# One-Wire_Write_Read.net
KiCad netlist of a schematic drawn in Altium Designer
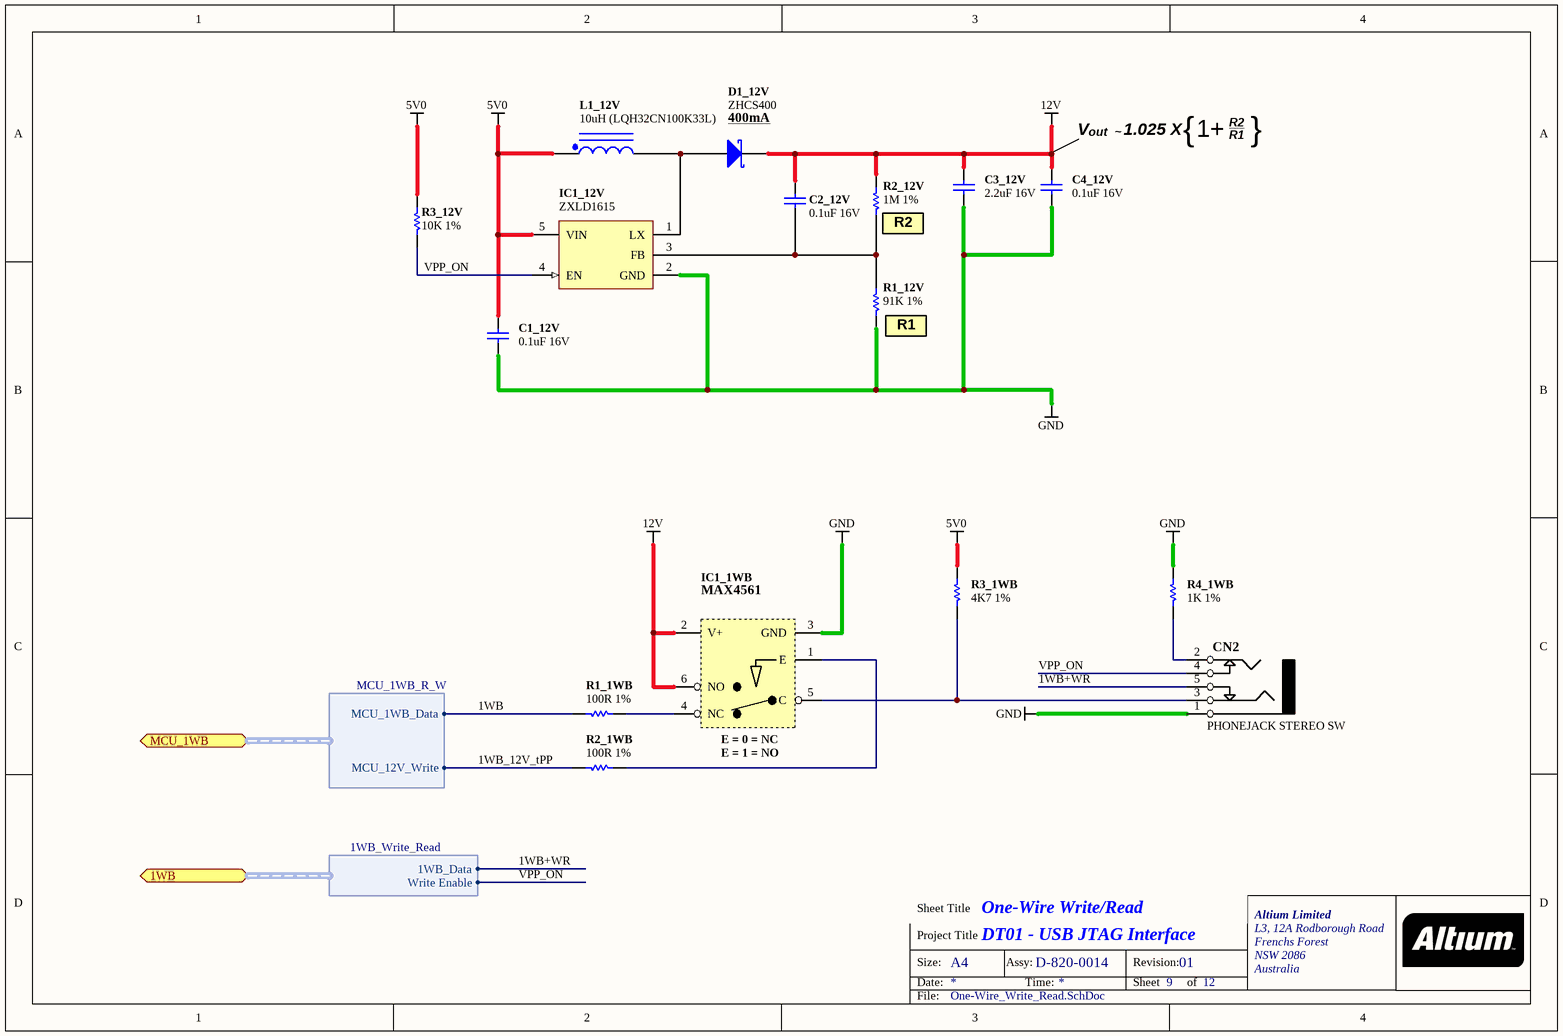
[diagram p0: One-Wire_Write_Read.SchDoc]

(export (version "E")
  (design (tool "Eeschema 10.0.6"))
  (components
    (comp (ref "C1_12V")
      (value "0.1uF 16V")
      (footprint "CAPC1005-STAR")
      (description "Capacitor, Ceramic, 0.1uF 10% 16V 0402 (1005) X7R")
      (fields (field (name "TOLERANCE") "10 %"))
      (libsource (lib "AltiumDesignLibrary") (part "CAP-NP"))
    )
    (comp (ref "C2_12V")
      (value "0.1uF 16V")
      (footprint "CAPC1005-STAR")
      (description "Capacitor, Ceramic, 0.1uF 10% 16V 0402 (1005) X7R")
      (fields (field (name "TOLERANCE") "10 %"))
      (libsource (lib "AltiumDesignLibrary") (part "CAP-NP"))
    )
    (comp (ref "C3_12V")
      (value "2.2uF 16V")
      (footprint "CAPC2012-STAR")
      (description "Capacitor, Ceramic, 2.2uF 10% 16V 0805 (2012) X5R")
      (fields (field (name "TOLERANCE") "10 %"))
      (libsource (lib "AltiumDesignLibrary") (part "CAP-NP"))
    )
    (comp (ref "C4_12V")
      (value "0.1uF 16V")
      (footprint "CAPC1005-STAR")
      (description "Capacitor, Ceramic, 0.1uF 10% 16V 0402 (1005) X7R")
      (fields (field (name "TOLERANCE") "10 %"))
      (libsource (lib "AltiumDesignLibrary") (part "CAP-NP"))
    )
    (comp (ref "CN2")
      (value "PHONEJACK STEREO SW")
      (footprint "STX-2550-5N-TR")
      (libsource (lib "AltiumDesignLibrary") (part "PHONEJACK STEREO SW"))
    )
    (comp (ref "D1_12V")
      (value "ZHCS400")
      (footprint "SOD323")
      (description "Schottky Diode, 400mA")
      (libsource (lib "AltiumDesignLibrary") (part "DIO-SCHOTTKY-1S"))
    )
    (comp (ref "IC1_1WB")
      (value "MAX4561")
      (footprint "SOT23-6")
      (description "±15kV ESD-Protected, Low-Voltage,  SPDT, CMOS Analog Switches")
      (libsource (lib "AltiumDesignLibrary") (part "MAX4561"))
    )
    (comp (ref "IC1_12V")
      (value "ZXLD1615")
      (footprint "SOT-23-5")
      (description "ADJUSTABLE DC-DC BOOST CONVERTER WITH INTERNAL SWITCH IN  TSOT23-5")
      (libsource (lib "AltiumDesignLibrary") (part "ZXLD1615"))
    )
    (comp (ref "L1_12V")
      (value "10uH (LQH32CN100K33L)")
      (footprint "3261")
      (description "Inductor, 10uH, 450mA, 0.3R, 1210 (3225) LQH32CN100K33L")
      (libsource (lib "AltiumDesignLibrary") (part "IND-IRON-DOT"))
    )
    (comp (ref "R1_1WB")
      (value "100R 1%")
      (footprint "RESC1005-STAR")
      (description "Resistor, 100R 1% 0402 (1005)")
      (fields (field (name "TOLERANCE") "1 %"))
      (libsource (lib "AltiumDesignLibrary") (part "RES"))
    )
    (comp (ref "R1_12V")
      (value "91K 1%")
      (footprint "RESC1005-STAR")
      (description "Resistor, 91K 1% 0402")
      (fields (field (name "TOLERANCE") "%"))
      (libsource (lib "AltiumDesignLibrary") (part "RES"))
    )
    (comp (ref "R2_1WB")
      (value "100R 1%")
      (footprint "RESC1005-STAR")
      (description "Resistor, 100R 1% 0402 (1005)")
      (fields (field (name "TOLERANCE") "1 %"))
      (libsource (lib "AltiumDesignLibrary") (part "RES"))
    )
    (comp (ref "R2_12V")
      (value "1M 1%")
      (footprint "RESC1005-STAR")
      (description "Resistor, 1M 1% 0402")
      (fields (field (name "TOLERANCE") "%"))
      (libsource (lib "AltiumDesignLibrary") (part "RES"))
    )
    (comp (ref "R3_1WB")
      (value "4K7 1%")
      (footprint "RESC1005-STAR")
      (description "Resistor, 4K7 1% 0402 (1005)")
      (fields (field (name "TOLERANCE") "1 %"))
      (libsource (lib "AltiumDesignLibrary") (part "RES"))
    )
    (comp (ref "R3_12V")
      (value "10K 1%")
      (footprint "RESC1005-STAR")
      (description "Resistor, 10K 1% 0402 (1005)")
      (fields (field (name "TOLERANCE") "1 %"))
      (libsource (lib "AltiumDesignLibrary") (part "RES"))
    )
    (comp (ref "R4_1WB")
      (value "1K 1%")
      (footprint "RESC1005-STAR")
      (description "Resistor, 1K 1% 0402 (1005)")
      (fields (field (name "TOLERANCE") "1 %"))
      (libsource (lib "AltiumDesignLibrary") (part "RES"))
    )
  )
  (nets
    (net (code "3") (name "/1WB") (class "Default")
      (node (ref "R1_1WB") (pin "1") (pinfunction "1_1") (pintype "passive"))
    )
    (net (code "4") (name "/1WB+WR") (class "Default") (node (ref "CN2") (pin "5") (pintype "passive")))
    (net (code "5") (name "/1WB_12V_tPP") (class "Default")
      (node (ref "R2_1WB") (pin "1") (pinfunction "1_1") (pintype "passive"))
    )
    (net (code "6") (name "/VPP_ON") (class "Default")
      (node (ref "CN2") (pin "4") (pintype "passive"))
      (node (ref "IC1_12V") (pin "4") (pinfunction "EN_4") (pintype "input"))
      (node (ref "R3_12V") (pin "2") (pinfunction "2_2") (pintype "passive"))
    )
    (net (code "9") (name "5V0") (class "Default")
      (node (ref "C1_12V") (pin "2") (pinfunction "2_2") (pintype "passive"))
      (node (ref "IC1_12V") (pin "5") (pinfunction "VIN_5") (pintype "power_in"))
      (node (ref "L1_12V") (pin "1") (pinfunction "1_1") (pintype "passive"))
      (node (ref "R3_12V") (pin "1") (pinfunction "1_1") (pintype "passive"))
      (node (ref "R3_1WB") (pin "2") (pinfunction "2_2") (pintype "passive"))
    )
    (net (code "10") (name "12V") (class "Default")
      (node (ref "C2_12V") (pin "2") (pinfunction "2_2") (pintype "passive"))
      (node (ref "C3_12V") (pin "2") (pinfunction "2_2") (pintype "passive"))
      (node (ref "C4_12V") (pin "2") (pinfunction "2_2") (pintype "passive"))
      (node (ref "D1_12V") (pin "2") (pinfunction "K_2") (pintype "passive"))
      (node (ref "IC1_1WB") (pin "2") (pinfunction "V+_2") (pintype "passive"))
      (node (ref "IC1_1WB") (pin "6") (pinfunction "NO_6") (pintype "passive"))
      (node (ref "R2_12V") (pin "2") (pinfunction "2_2") (pintype "passive"))
    )
    (net (code "11") (name "GND") (class "Default")
      (node (ref "C1_12V") (pin "1") (pinfunction "1_1") (pintype "passive"))
      (node (ref "C3_12V") (pin "1") (pinfunction "1_1") (pintype "passive"))
      (node (ref "C4_12V") (pin "1") (pinfunction "1_1") (pintype "passive"))
      (node (ref "CN2") (pin "1") (pintype "passive"))
      (node (ref "IC1_12V") (pin "2") (pinfunction "GND_2") (pintype "power_in"))
      (node (ref "IC1_1WB") (pin "3") (pinfunction "GND_3") (pintype "passive"))
      (node (ref "R1_12V") (pin "1") (pinfunction "1_1") (pintype "passive"))
      (node (ref "R4_1WB") (pin "2") (pinfunction "2_2") (pintype "passive"))
    )
    (net (code "12") (name "Net-(CN2-Pad2)") (class "Default")
      (node (ref "CN2") (pin "2") (pintype "passive"))
      (node (ref "R4_1WB") (pin "1") (pinfunction "1_1") (pintype "passive"))
    )
    (net (code "13") (name "Net-(D1_12V-A)") (class "Default")
      (node (ref "D1_12V") (pin "1") (pinfunction "A_1") (pintype "passive"))
      (node (ref "IC1_12V") (pin "1") (pinfunction "LX_1") (pintype "open_collector"))
      (node (ref "L1_12V") (pin "2") (pinfunction "2_2") (pintype "passive"))
    )
    (net (code "14") (name "Net-(IC1_1WB-C)") (class "Default")
      (node (ref "CN2") (pin "3") (pintype "passive"))
      (node (ref "IC1_1WB") (pin "5") (pinfunction "C_5") (pintype "passive"))
      (node (ref "R3_1WB") (pin "1") (pinfunction "1_1") (pintype "passive"))
    )
    (net (code "15") (name "Net-(IC1_1WB-E)") (class "Default")
      (node (ref "IC1_1WB") (pin "1") (pinfunction "E_1") (pintype "passive"))
      (node (ref "R2_1WB") (pin "2") (pinfunction "2_2") (pintype "passive"))
    )
    (net (code "16") (name "Net-(IC1_1WB-NC)") (class "Default")
      (node (ref "IC1_1WB") (pin "4") (pinfunction "NC_4") (pintype "passive"))
      (node (ref "R1_1WB") (pin "2") (pinfunction "2_2") (pintype "passive"))
    )
    (net (code "17") (name "Net-(IC1_12V-FB)") (class "Default")
      (node (ref "C2_12V") (pin "1") (pinfunction "1_1") (pintype "passive"))
      (node (ref "IC1_12V") (pin "3") (pinfunction "FB_3") (pintype "open_collector"))
      (node (ref "R1_12V") (pin "2") (pinfunction "2_2") (pintype "passive"))
      (node (ref "R2_12V") (pin "1") (pinfunction "1_1") (pintype "passive"))
    )
  )
)
